# Processor_Unit.net
KiCad netlist of a schematic drawn in Altium Designer
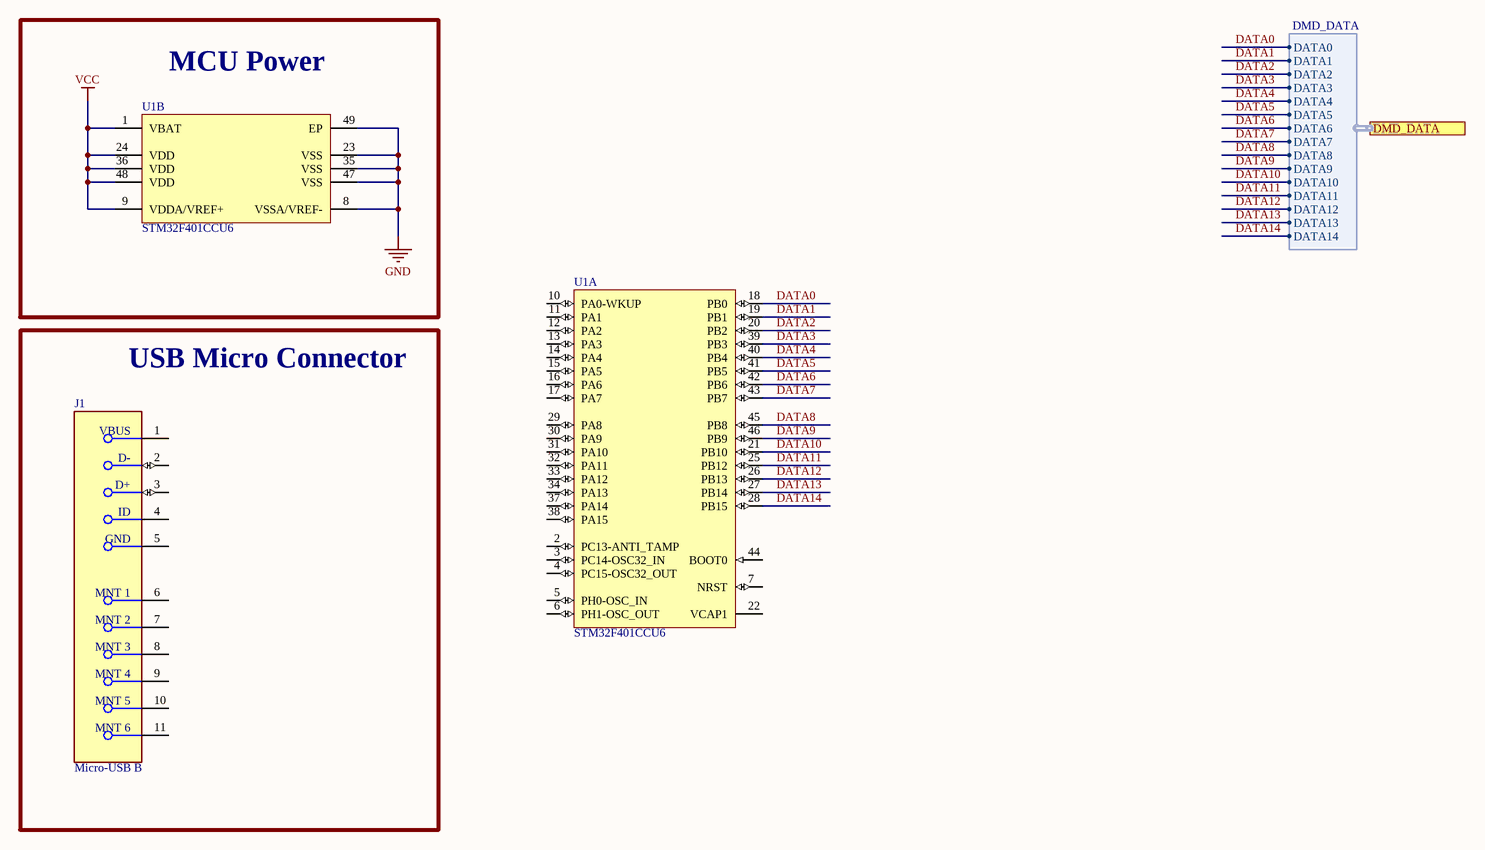
[diagram p0: Processor_Unit.SchDoc]

(export (version "E")
  (design (tool "Eeschema 10.0.6"))
  (components
    (comp (ref "J1")
      (value "Micro-USB B")
      (description "Micro-USB B Receptacle with Flange, Bottom Mount, Surface Mount, Lead-Free")
      (fields (field (name "MANUFACTURER") "Molex") (field (name "MANUFACTURER PART NUMBER") "47346-0001"))
      (libsource (lib "afra") (part "47346-0001"))
    )
    (comp (ref "U1")
      (value "STM32F401CCU6")
      (footprint "STM-UFQFPN48_N")
      (fields (field (name "MANUFACTURER") "STMicroelectronics"))
      (libsource (lib "afra") (part "STM32F401CCU6"))
    )
  )
  (nets
    (net (code "2") (name "/DATA0") (class "Default")
      (node (ref "U1") (pin "18") (pinfunction "PB0_18") (pintype "bidirectional"))
    )
    (net (code "3") (name "/DATA1") (class "Default")
      (node (ref "U1") (pin "19") (pinfunction "PB1_19") (pintype "bidirectional"))
    )
    (net (code "4") (name "/DATA2") (class "Default")
      (node (ref "U1") (pin "20") (pinfunction "PB2_20") (pintype "bidirectional"))
    )
    (net (code "5") (name "/DATA3") (class "Default")
      (node (ref "U1") (pin "39") (pinfunction "PB3_39") (pintype "bidirectional"))
    )
    (net (code "6") (name "/DATA4") (class "Default")
      (node (ref "U1") (pin "40") (pinfunction "PB4_40") (pintype "bidirectional"))
    )
    (net (code "7") (name "/DATA5") (class "Default")
      (node (ref "U1") (pin "41") (pinfunction "PB5_41") (pintype "bidirectional"))
    )
    (net (code "8") (name "/DATA6") (class "Default")
      (node (ref "U1") (pin "42") (pinfunction "PB6_42") (pintype "bidirectional"))
    )
    (net (code "9") (name "/DATA7") (class "Default")
      (node (ref "U1") (pin "43") (pinfunction "PB7_43") (pintype "bidirectional"))
    )
    (net (code "10") (name "/DATA8") (class "Default")
      (node (ref "U1") (pin "45") (pinfunction "PB8_45") (pintype "bidirectional"))
    )
    (net (code "11") (name "/DATA9") (class "Default")
      (node (ref "U1") (pin "46") (pinfunction "PB9_46") (pintype "bidirectional"))
    )
    (net (code "12") (name "/DATA10") (class "Default")
      (node (ref "U1") (pin "21") (pinfunction "PB10_21") (pintype "bidirectional"))
    )
    (net (code "13") (name "/DATA11") (class "Default")
      (node (ref "U1") (pin "25") (pinfunction "PB12_25") (pintype "bidirectional"))
    )
    (net (code "14") (name "/DATA12") (class "Default")
      (node (ref "U1") (pin "26") (pinfunction "PB13_26") (pintype "bidirectional"))
    )
    (net (code "15") (name "/DATA13") (class "Default")
      (node (ref "U1") (pin "27") (pinfunction "PB14_27") (pintype "bidirectional"))
    )
    (net (code "16") (name "/DATA14") (class "Default")
      (node (ref "U1") (pin "28") (pinfunction "PB15_28") (pintype "bidirectional"))
    )
    (net (code "18") (name "GND") (class "Default")
      (node (ref "U1") (pin "23") (pinfunction "VSS_23") (pintype "power_in"))
      (node (ref "U1") (pin "35") (pinfunction "VSS_35") (pintype "power_in"))
      (node (ref "U1") (pin "47") (pinfunction "VSS_47") (pintype "power_in"))
      (node (ref "U1") (pin "49") (pinfunction "EP_49") (pintype "power_in"))
      (node (ref "U1") (pin "8") (pinfunction "VSSA/VREF-_8") (pintype "power_in"))
    )
    (net (code "19") (name "VCC") (class "Default")
      (node (ref "U1") (pin "1") (pinfunction "VBAT_1") (pintype "power_in"))
      (node (ref "U1") (pin "24") (pinfunction "VDD_24") (pintype "power_in"))
      (node (ref "U1") (pin "36") (pinfunction "VDD_36") (pintype "power_in"))
      (node (ref "U1") (pin "48") (pinfunction "VDD_48") (pintype "power_in"))
      (node (ref "U1") (pin "9") (pinfunction "VDDA/VREF+_9") (pintype "power_in"))
    )
    (net (code "20") (name "unconnected-(J1-D+-Pad3)") (class "Default")
      (node (ref "J1") (pin "3") (pinfunction "D+_3") (pintype "bidirectional"))
    )
    (net (code "21") (name "unconnected-(J1-D--Pad2)") (class "Default")
      (node (ref "J1") (pin "2") (pinfunction "D-_2") (pintype "bidirectional"))
    )
    (net (code "22") (name "unconnected-(J1-GND-Pad5)") (class "Default")
      (node (ref "J1") (pin "5") (pinfunction "GND_5") (pintype "power_in"))
    )
    (net (code "23") (name "unconnected-(J1-ID-Pad4)") (class "Default")
      (node (ref "J1") (pin "4") (pinfunction "ID_4") (pintype "passive"))
    )
    (net (code "24") (name "unconnected-(J1-MNT_1-Pad6)") (class "Default")
      (node (ref "J1") (pin "6") (pinfunction "MNT_1_6") (pintype "passive"))
    )
    (net (code "25") (name "unconnected-(J1-MNT_2-Pad7)") (class "Default")
      (node (ref "J1") (pin "7") (pinfunction "MNT_2_7") (pintype "passive"))
    )
    (net (code "26") (name "unconnected-(J1-MNT_3-Pad8)") (class "Default")
      (node (ref "J1") (pin "8") (pinfunction "MNT_3_8") (pintype "passive"))
    )
    (net (code "27") (name "unconnected-(J1-MNT_4-Pad9)") (class "Default")
      (node (ref "J1") (pin "9") (pinfunction "MNT_4_9") (pintype "passive"))
    )
    (net (code "28") (name "unconnected-(J1-MNT_5-Pad10)") (class "Default")
      (node (ref "J1") (pin "10") (pinfunction "MNT_5_10") (pintype "passive"))
    )
    (net (code "29") (name "unconnected-(J1-MNT_6-Pad11)") (class "Default")
      (node (ref "J1") (pin "11") (pinfunction "MNT_6_11") (pintype "passive"))
    )
    (net (code "30") (name "unconnected-(J1-VBUS-Pad1)") (class "Default")
      (node (ref "J1") (pin "1") (pinfunction "VBUS_1") (pintype "power_in"))
    )
    (net (code "31") (name "unconnected-(U1A-BOOT0-Pad44)") (class "Default")
      (node (ref "U1") (pin "44") (pinfunction "BOOT0_44") (pintype "input"))
    )
    (net (code "32") (name "unconnected-(U1A-NRST-Pad7)") (class "Default")
      (node (ref "U1") (pin "7") (pinfunction "NRST_7") (pintype "bidirectional"))
    )
    (net (code "33") (name "unconnected-(U1A-PA0-WKUP-Pad10)") (class "Default")
      (node (ref "U1") (pin "10") (pinfunction "PA0-WKUP_10") (pintype "bidirectional"))
    )
    (net (code "34") (name "unconnected-(U1A-PA1-Pad11)") (class "Default")
      (node (ref "U1") (pin "11") (pinfunction "PA1_11") (pintype "bidirectional"))
    )
    (net (code "35") (name "unconnected-(U1A-PA2-Pad12)") (class "Default")
      (node (ref "U1") (pin "12") (pinfunction "PA2_12") (pintype "bidirectional"))
    )
    (net (code "36") (name "unconnected-(U1A-PA3-Pad13)") (class "Default")
      (node (ref "U1") (pin "13") (pinfunction "PA3_13") (pintype "bidirectional"))
    )
    (net (code "37") (name "unconnected-(U1A-PA4-Pad14)") (class "Default")
      (node (ref "U1") (pin "14") (pinfunction "PA4_14") (pintype "bidirectional"))
    )
    (net (code "38") (name "unconnected-(U1A-PA5-Pad15)") (class "Default")
      (node (ref "U1") (pin "15") (pinfunction "PA5_15") (pintype "bidirectional"))
    )
    (net (code "39") (name "unconnected-(U1A-PA6-Pad16)") (class "Default")
      (node (ref "U1") (pin "16") (pinfunction "PA6_16") (pintype "bidirectional"))
    )
    (net (code "40") (name "unconnected-(U1A-PA7-Pad17)") (class "Default")
      (node (ref "U1") (pin "17") (pinfunction "PA7_17") (pintype "bidirectional"))
    )
    (net (code "41") (name "unconnected-(U1A-PA8-Pad29)") (class "Default")
      (node (ref "U1") (pin "29") (pinfunction "PA8_29") (pintype "bidirectional"))
    )
    (net (code "42") (name "unconnected-(U1A-PA9-Pad30)") (class "Default")
      (node (ref "U1") (pin "30") (pinfunction "PA9_30") (pintype "bidirectional"))
    )
    (net (code "43") (name "unconnected-(U1A-PA10-Pad31)") (class "Default")
      (node (ref "U1") (pin "31") (pinfunction "PA10_31") (pintype "bidirectional"))
    )
    (net (code "44") (name "unconnected-(U1A-PA11-Pad32)") (class "Default")
      (node (ref "U1") (pin "32") (pinfunction "PA11_32") (pintype "bidirectional"))
    )
    (net (code "45") (name "unconnected-(U1A-PA12-Pad33)") (class "Default")
      (node (ref "U1") (pin "33") (pinfunction "PA12_33") (pintype "bidirectional"))
    )
    (net (code "46") (name "unconnected-(U1A-PA13-Pad34)") (class "Default")
      (node (ref "U1") (pin "34") (pinfunction "PA13_34") (pintype "bidirectional"))
    )
    (net (code "47") (name "unconnected-(U1A-PA14-Pad37)") (class "Default")
      (node (ref "U1") (pin "37") (pinfunction "PA14_37") (pintype "bidirectional"))
    )
    (net (code "48") (name "unconnected-(U1A-PA15-Pad38)") (class "Default")
      (node (ref "U1") (pin "38") (pinfunction "PA15_38") (pintype "bidirectional"))
    )
    (net (code "49") (name "unconnected-(U1A-PC13-ANTI_TAMP-Pad2)") (class "Default")
      (node (ref "U1") (pin "2") (pinfunction "PC13-ANTI_TAMP_2") (pintype "bidirectional"))
    )
    (net (code "50") (name "unconnected-(U1A-PC14-OSC32_IN-Pad3)") (class "Default")
      (node (ref "U1") (pin "3") (pinfunction "PC14-OSC32_IN_3") (pintype "bidirectional"))
    )
    (net (code "51") (name "unconnected-(U1A-PC15-OSC32_OUT-Pad4)") (class "Default")
      (node (ref "U1") (pin "4") (pinfunction "PC15-OSC32_OUT_4") (pintype "bidirectional"))
    )
    (net (code "52") (name "unconnected-(U1A-PH0-OSC_IN-Pad5)") (class "Default")
      (node (ref "U1") (pin "5") (pinfunction "PH0-OSC_IN_5") (pintype "bidirectional"))
    )
    (net (code "53") (name "unconnected-(U1A-PH1-OSC_OUT-Pad6)") (class "Default")
      (node (ref "U1") (pin "6") (pinfunction "PH1-OSC_OUT_6") (pintype "bidirectional"))
    )
    (net (code "54") (name "unconnected-(U1A-VCAP1-Pad22)") (class "Default")
      (node (ref "U1") (pin "22") (pinfunction "VCAP1_22") (pintype "power_in"))
    )
  )
)
